# SparkFun_NEO-M8T.net
KiCad netlist of a schematic drawn in EAGLE
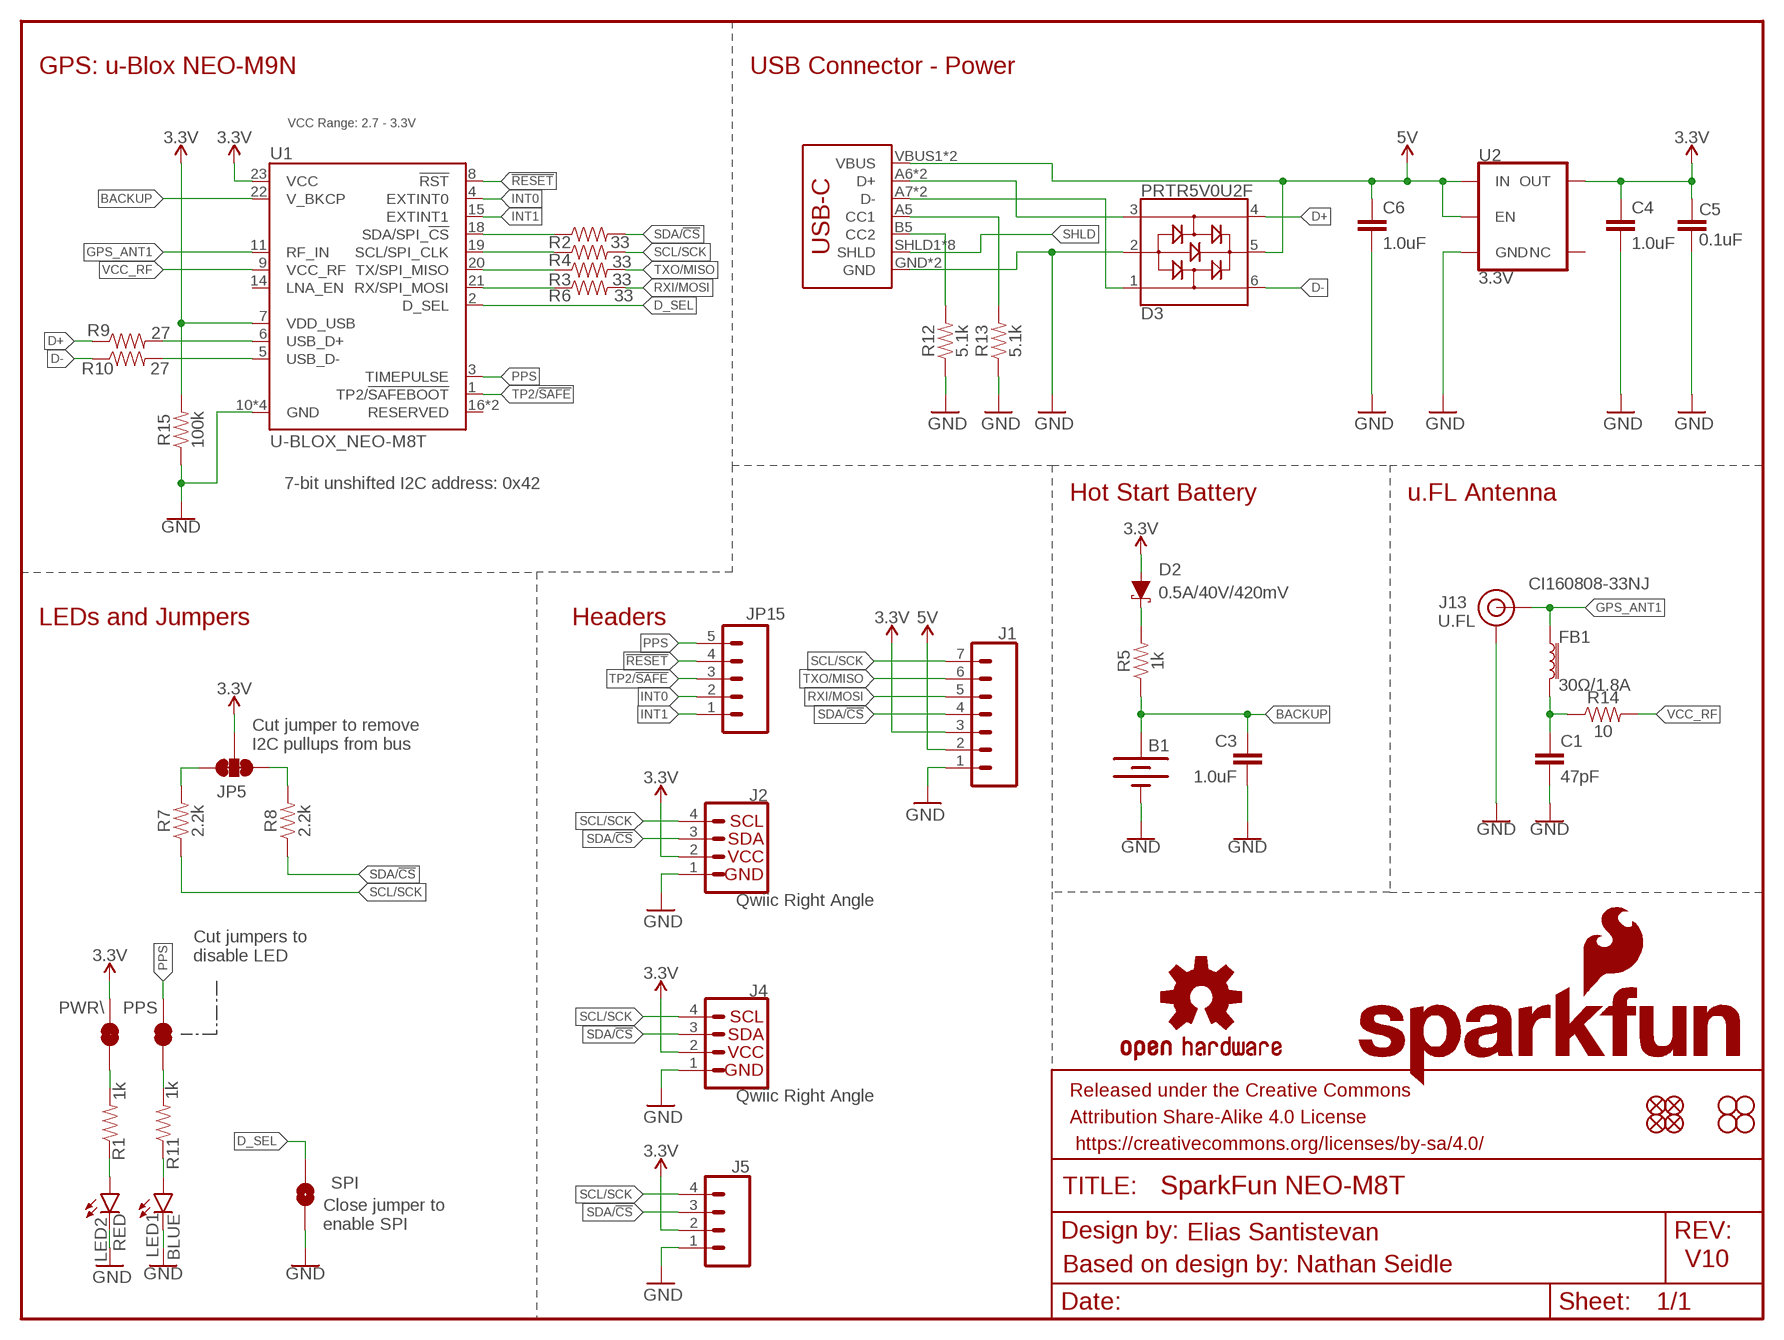
[diagram p0: schematic, sheet 1]

(export (version "E")
  (design (tool "Eeschema 10.0.6"))
  (components
    (comp (ref "B1")
      (value "6.8MM_COIN_CELL")
      (footprint "eagle-import:ML414H_IV01E")
      (libsource (lib "eagle-import") (part "ML414H_IV01E_BATTERY"))
    )
    (comp (ref "C1")
      (value "47pF")
      (footprint "eagle-import:0603")
      (libsource (lib "eagle-import") (part "47PF-0603-50V-5%"))
    )
    (comp (ref "C3")
      (value "1.0uF")
      (footprint "eagle-import:0603")
      (libsource (lib "eagle-import") (part "1.0UF-0603-16V-10%"))
    )
    (comp (ref "C4")
      (value "1.0uF")
      (footprint "eagle-import:0603")
      (libsource (lib "eagle-import") (part "1.0UF-0603-16V-10%"))
    )
    (comp (ref "C5")
      (value "0.1uF")
      (footprint "eagle-import:0603")
      (libsource (lib "eagle-import") (part "0.1UF-0603-25V-(+80/-20%)"))
    )
    (comp (ref "C6")
      (value "1.0uF")
      (footprint "eagle-import:0603")
      (libsource (lib "eagle-import") (part "1.0UF-0603-16V-10%"))
    )
    (comp (ref "D2")
      (value "0.5A/40V/420mV")
      (footprint "eagle-import:SOD-323")
      (libsource (lib "eagle-import") (part "DIODE-SCHOTTKY-PMEG4005EJ"))
    )
    (comp (ref "D3")
      (value "PRTR5V0U2F")
      (footprint "eagle-import:SOT886")
      (libsource (lib "eagle-import") (part "PRTR5V0U2F"))
    )
    (comp (ref "FB1")
      (value "30Ω/1.8A")
      (footprint "eagle-import:0603")
      (libsource (lib "eagle-import") (part "FERRITE_BEAD-0603"))
    )
    (comp (ref "FRAME1")
      (value "FRAME-LETTER")
      (footprint "eagle-import:CREATIVE_COMMONS")
      (libsource (lib "eagle-import") (part "FRAME-LETTER"))
    )
    (comp (ref "J1")
      (value "CONN_07NO_SILK")
      (footprint "eagle-import:1X07_NO_SILK")
      (libsource (lib "eagle-import") (part "CONN_07NO_SILK"))
    )
    (comp (ref "J2")
      (value "Qwiic Right Angle")
      (footprint "eagle-import:JST04_1MM_RA")
      (libsource (lib "eagle-import") (part "I2C_STANDARDQWIIC"))
    )
    (comp (ref "J3")
      (value "USB_C2-LAYER")
      (footprint "eagle-import:USB-C-16P")
      (libsource (lib "eagle-import") (part "USB_C2-LAYER"))
    )
    (comp (ref "J4")
      (value "Qwiic Right Angle")
      (footprint "eagle-import:JST04_1MM_RA")
      (libsource (lib "eagle-import") (part "I2C_STANDARDQWIIC"))
    )
    (comp (ref "J5")
      (value "CONN_041X04_NO_SILK")
      (footprint "eagle-import:1X04_NO_SILK")
      (libsource (lib "eagle-import") (part "CONN_041X04_NO_SILK"))
    )
    (comp (ref "J13")
      (value "U.FL")
      (footprint "eagle-import:U.FL")
      (libsource (lib "eagle-import") (part "U.FL2PIN"))
    )
    (comp (ref "JP5")
      (value "JUMPER-SMT_3_2-NC_TRACE_SILK")
      (footprint "eagle-import:SMT-JUMPER_3_2-NC_TRACE_SILK")
      (libsource (lib "eagle-import") (part "JUMPER-SMT_3_2-NC_TRACE_SILK"))
    )
    (comp (ref "JP15")
      (value "CONN_05NO_SILK")
      (footprint "eagle-import:1X05_NO_SILK")
      (libsource (lib "eagle-import") (part "CONN_05NO_SILK"))
    )
    (comp (ref "JP21")
      (value "FIDUCIALUFIDUCIAL")
      (footprint "eagle-import:MICRO-FIDUCIAL")
      (libsource (lib "eagle-import") (part "FIDUCIALUFIDUCIAL"))
    )
    (comp (ref "JP31")
      (value "STAND-OFF")
      (footprint "eagle-import:STAND-OFF")
      (libsource (lib "eagle-import") (part "STAND-OFF"))
    )
    (comp (ref "JP41")
      (value "STAND-OFF")
      (footprint "eagle-import:STAND-OFF")
      (libsource (lib "eagle-import") (part "STAND-OFF"))
    )
    (comp (ref "JP61")
      (value "FIDUCIALUFIDUCIAL")
      (footprint "eagle-import:MICRO-FIDUCIAL")
      (libsource (lib "eagle-import") (part "FIDUCIALUFIDUCIAL"))
    )
    (comp (ref "JP71")
      (value "FIDUCIALUFIDUCIAL")
      (footprint "eagle-import:MICRO-FIDUCIAL")
      (libsource (lib "eagle-import") (part "FIDUCIALUFIDUCIAL"))
    )
    (comp (ref "JP81")
      (value "FIDUCIALUFIDUCIAL")
      (footprint "eagle-import:MICRO-FIDUCIAL")
      (libsource (lib "eagle-import") (part "FIDUCIALUFIDUCIAL"))
    )
    (comp (ref "JP91")
      (value "STAND-OFF")
      (footprint "eagle-import:STAND-OFF")
      (libsource (lib "eagle-import") (part "STAND-OFF"))
    )
    (comp (ref "JP101")
      (value "STAND-OFF")
      (footprint "eagle-import:STAND-OFF")
      (libsource (lib "eagle-import") (part "STAND-OFF"))
    )
    (comp (ref "LED1")
      (value "BLUE")
      (footprint "eagle-import:LED-0603")
      (libsource (lib "eagle-import") (part "LED-BLUE0603"))
    )
    (comp (ref "LED2")
      (value "RED")
      (footprint "eagle-import:LED-0603")
      (libsource (lib "eagle-import") (part "LED-RED0603"))
    )
    (comp (ref "LOGO1")
      (value "OSHW-LOGOMINI")
      (footprint "eagle-import:OSHW-LOGO-MINI")
      (libsource (lib "eagle-import") (part "OSHW-LOGOMINI"))
    )
    (comp (ref "LOGO2")
      (value "SFE_LOGO_NAME_FLAME.1_INCH")
      (footprint "eagle-import:SFE_LOGO_NAME_FLAME_.1")
      (libsource (lib "eagle-import") (part "SFE_LOGO_NAME_FLAME.1_INCH"))
    )
    (comp (ref "PPS")
      (value "JUMPER-SMT_2_NC_TRACE_SILK")
      (footprint "eagle-import:SMT-JUMPER_2_NC_TRACE_SILK")
      (libsource (lib "eagle-import") (part "JUMPER-SMT_2_NC_TRACE_SILK"))
    )
    (comp (ref "PWR\\")
      (value "JUMPER-SMT_2_NC_TRACE_SILK")
      (footprint "eagle-import:SMT-JUMPER_2_NC_TRACE_SILK")
      (libsource (lib "eagle-import") (part "JUMPER-SMT_2_NC_TRACE_SILK"))
    )
    (comp (ref "R1")
      (value "1k")
      (footprint "eagle-import:0603")
      (libsource (lib "eagle-import") (part "1KOHM-0603-1/10W-1%"))
    )
    (comp (ref "R2")
      (value "33")
      (footprint "eagle-import:0603")
      (libsource (lib "eagle-import") (part "33OHM-0603-1/10W-1%"))
    )
    (comp (ref "R3")
      (value "33")
      (footprint "eagle-import:0603")
      (libsource (lib "eagle-import") (part "33OHM-0603-1/10W-1%"))
    )
    (comp (ref "R4")
      (value "33")
      (footprint "eagle-import:0603")
      (libsource (lib "eagle-import") (part "33OHM-0603-1/10W-1%"))
    )
    (comp (ref "R5")
      (value "1k")
      (footprint "eagle-import:0603")
      (libsource (lib "eagle-import") (part "1KOHM-0603-1/10W-1%"))
    )
    (comp (ref "R6")
      (value "33")
      (footprint "eagle-import:0603")
      (libsource (lib "eagle-import") (part "33OHM-0603-1/10W-1%"))
    )
    (comp (ref "R7")
      (value "2.2k")
      (footprint "eagle-import:0603")
      (libsource (lib "eagle-import") (part "2.2KOHM-0603-1/10W-1%"))
    )
    (comp (ref "R8")
      (value "2.2k")
      (footprint "eagle-import:0603")
      (libsource (lib "eagle-import") (part "2.2KOHM-0603-1/10W-1%"))
    )
    (comp (ref "R9")
      (value "27")
      (footprint "eagle-import:0603")
      (libsource (lib "eagle-import") (part "27OHM-0603-1/10W-1%"))
    )
    (comp (ref "R10")
      (value "27")
      (footprint "eagle-import:0603")
      (libsource (lib "eagle-import") (part "27OHM-0603-1/10W-1%"))
    )
    (comp (ref "R11")
      (value "1k")
      (footprint "eagle-import:0603")
      (libsource (lib "eagle-import") (part "1KOHM-0603-1/10W-1%"))
    )
    (comp (ref "R12")
      (value "5.1k")
      (footprint "eagle-import:0603")
      (libsource (lib "eagle-import") (part "5.1KOHM5.1KOHM-0603-1/10W-1%"))
    )
    (comp (ref "R13")
      (value "5.1k")
      (footprint "eagle-import:0603")
      (libsource (lib "eagle-import") (part "5.1KOHM5.1KOHM-0603-1/10W-1%"))
    )
    (comp (ref "R14")
      (value "10")
      (footprint "eagle-import:0603")
      (libsource (lib "eagle-import") (part "10OHM-0603-1/10W-1%"))
    )
    (comp (ref "R15")
      (value "100k")
      (footprint "eagle-import:0603")
      (libsource (lib "eagle-import") (part "100KOHM-0603-1/10W-1%"))
    )
    (comp (ref "SPI")
      (value "JUMPER-SMT_2_NO_SILK")
      (footprint "eagle-import:SMT-JUMPER_2_NO_SILK")
      (libsource (lib "eagle-import") (part "JUMPER-SMT_2_NO_SILK"))
    )
    (comp (ref "U1")
      (value "U-BLOX_NEO-M8T")
      (footprint "eagle-import:NEO-M9N_M8T")
      (libsource (lib "eagle-import") (part "U-BLOX_NEO-M8T"))
    )
    (comp (ref "U2")
      (value "3.3V")
      (footprint "eagle-import:SOT23-5")
      (libsource (lib "eagle-import") (part "V_REG_AP2112K-3.3V"))
    )
  )
  (nets
    (net (code "1") (name "/SDA{slash}~{CS}") (class "Default")
      (node (ref "J1") (pin "4") (pinfunction "4_4") (pintype "passive"))
      (node (ref "J2") (pin "3") (pinfunction "3_3") (pintype "passive"))
      (node (ref "J4") (pin "3") (pinfunction "3_3") (pintype "passive"))
      (node (ref "J5") (pin "3") (pinfunction "3_3") (pintype "passive"))
      (node (ref "R2") (pin "2") (pinfunction "2_2") (pintype "passive"))
      (node (ref "R8") (pin "1") (pinfunction "1_1") (pintype "passive"))
    )
    (net (code "2") (name "/TP2{slash}~{SAFE}") (class "Default")
      (node (ref "JP15") (pin "3") (pinfunction "3_3") (pintype "passive"))
      (node (ref "U1") (pin "1") (pinfunction "TP2/~{SAFEBOOT}_1") (pintype "bidirectional"))
    )
    (net (code "3") (name "/~{RESET}") (class "Default")
      (node (ref "JP15") (pin "4") (pinfunction "4_4") (pintype "passive"))
      (node (ref "U1") (pin "8") (pinfunction "~{RST}_8") (pintype "bidirectional"))
    )
    (net (code "4") (name "3.3V") (class "Default")
      (node (ref "C4") (pin "1") (pinfunction "1_1") (pintype "passive"))
      (node (ref "C5") (pin "2") (pinfunction "2_2") (pintype "passive"))
      (node (ref "D2") (pin "A") (pinfunction "A_A") (pintype "passive"))
      (node (ref "J1") (pin "3") (pinfunction "3_3") (pintype "passive"))
      (node (ref "J2") (pin "2") (pinfunction "2_2") (pintype "power_in"))
      (node (ref "J4") (pin "2") (pinfunction "2_2") (pintype "power_in"))
      (node (ref "J5") (pin "2") (pinfunction "2_2") (pintype "passive"))
      (node (ref "JP5") (pin "2") (pinfunction "2_2") (pintype "passive"))
      (node (ref "PWR\\") (pin "2") (pinfunction "2_2") (pintype "passive"))
      (node (ref "R15") (pin "2") (pinfunction "2_2") (pintype "passive"))
      (node (ref "U1") (pin "23") (pinfunction "VCC_23") (pintype "bidirectional"))
      (node (ref "U1") (pin "7") (pinfunction "VDD_USB_7") (pintype "bidirectional"))
      (node (ref "U2") (pin "5") (pinfunction "OUT_5") (pintype "passive"))
    )
    (net (code "5") (name "5V") (class "Default")
      (node (ref "C6") (pin "1") (pinfunction "1_1") (pintype "passive"))
      (node (ref "D3") (pin "5") (pinfunction "5_5") (pintype "bidirectional"))
      (node (ref "J1") (pin "2") (pinfunction "2_2") (pintype "passive"))
      (node (ref "J3") (pin "VBUS1") (pinfunction "VBUS_VBUS1") (pintype "bidirectional"))
      (node (ref "J3") (pin "VBUS2") (pinfunction "VBUS_VBUS2") (pintype "bidirectional"))
      (node (ref "U2") (pin "1") (pinfunction "IN_1") (pintype "input"))
      (node (ref "U2") (pin "3") (pinfunction "EN_3") (pintype "input"))
    )
    (net (code "6") (name "BACKUP") (class "Default")
      (node (ref "B1") (pin "+") (pinfunction "+_+") (pintype "power_in"))
      (node (ref "C3") (pin "1") (pinfunction "1_1") (pintype "passive"))
      (node (ref "R5") (pin "1") (pinfunction "1_1") (pintype "passive"))
      (node (ref "U1") (pin "22") (pinfunction "V_BKCP_22") (pintype "bidirectional"))
    )
    (net (code "7") (name "D+") (class "Default")
      (node (ref "D3") (pin "4") (pinfunction "4_4") (pintype "bidirectional"))
      (node (ref "R9") (pin "1") (pinfunction "1_1") (pintype "passive"))
    )
    (net (code "8") (name "D-") (class "Default")
      (node (ref "D3") (pin "6") (pinfunction "6_6") (pintype "bidirectional"))
      (node (ref "R10") (pin "1") (pinfunction "1_1") (pintype "passive"))
    )
    (net (code "9") (name "D_SEL") (class "Default")
      (node (ref "SPI") (pin "2") (pinfunction "2_2") (pintype "passive"))
      (node (ref "U1") (pin "2") (pinfunction "D_SEL_2") (pintype "bidirectional"))
    )
    (net (code "10") (name "GND") (class "Default")
      (node (ref "B1") (pin "-") (pinfunction "-_-") (pintype "power_in"))
      (node (ref "C1") (pin "2") (pinfunction "2_2") (pintype "passive"))
      (node (ref "C3") (pin "2") (pinfunction "2_2") (pintype "passive"))
      (node (ref "C4") (pin "2") (pinfunction "2_2") (pintype "passive"))
      (node (ref "C5") (pin "1") (pinfunction "1_1") (pintype "passive"))
      (node (ref "C6") (pin "2") (pinfunction "2_2") (pintype "passive"))
      (node (ref "D3") (pin "2") (pinfunction "2_2") (pintype "bidirectional"))
      (node (ref "J1") (pin "1") (pinfunction "1_1") (pintype "passive"))
      (node (ref "J13") (pin "1") (pinfunction "GND_1") (pintype "bidirectional"))
      (node (ref "J13") (pin "2") (pinfunction "GND_2") (pintype "bidirectional"))
      (node (ref "J2") (pin "1") (pinfunction "1_1") (pintype "power_in"))
      (node (ref "J3") (pin "GND") (pinfunction "GND_GND") (pintype "bidirectional"))
      (node (ref "J3") (pin "GND2") (pinfunction "GND_GND2") (pintype "bidirectional"))
      (node (ref "J4") (pin "1") (pinfunction "1_1") (pintype "power_in"))
      (node (ref "J5") (pin "1") (pinfunction "1_1") (pintype "passive"))
      (node (ref "LED1") (pin "C") (pinfunction "C_C") (pintype "passive"))
      (node (ref "LED2") (pin "C") (pinfunction "C_C") (pintype "passive"))
      (node (ref "R12") (pin "1") (pinfunction "1_1") (pintype "passive"))
      (node (ref "R13") (pin "1") (pinfunction "1_1") (pintype "passive"))
      (node (ref "R15") (pin "1") (pinfunction "1_1") (pintype "passive"))
      (node (ref "SPI") (pin "1") (pinfunction "1_1") (pintype "passive"))
      (node (ref "U1") (pin "10") (pinfunction "GND_10") (pintype "bidirectional"))
      (node (ref "U1") (pin "12") (pinfunction "GND_12") (pintype "bidirectional"))
      (node (ref "U1") (pin "13") (pinfunction "GND_13") (pintype "bidirectional"))
      (node (ref "U1") (pin "24") (pinfunction "GND_24") (pintype "bidirectional"))
      (node (ref "U2") (pin "2") (pinfunction "GND_2") (pintype "input"))
    )
    (net (code "11") (name "GPS_ANT1") (class "Default")
      (node (ref "FB1") (pin "1") (pinfunction "1_1") (pintype "passive"))
      (node (ref "J13") (pin "FEED") (pinfunction "SIGNAL_FEED") (pintype "bidirectional"))
      (node (ref "U1") (pin "11") (pinfunction "RF_IN_11") (pintype "bidirectional"))
    )
    (net (code "12") (name "INT0") (class "Default")
      (node (ref "JP15") (pin "2") (pinfunction "2_2") (pintype "passive"))
      (node (ref "U1") (pin "4") (pinfunction "EXTINT0_4") (pintype "bidirectional"))
    )
    (net (code "13") (name "INT1") (class "Default")
      (node (ref "JP15") (pin "1") (pinfunction "1_1") (pintype "passive"))
      (node (ref "U1") (pin "15") (pinfunction "EXTINT1_15") (pintype "bidirectional"))
    )
    (net (code "14") (name "Net-(C1-Pad1)") (class "Default")
      (node (ref "C1") (pin "1") (pinfunction "1_1") (pintype "passive"))
      (node (ref "FB1") (pin "2") (pinfunction "2_2") (pintype "passive"))
      (node (ref "R14") (pin "1") (pinfunction "1_1") (pintype "passive"))
    )
    (net (code "15") (name "Net-(D2-PadC)") (class "Default")
      (node (ref "D2") (pin "C") (pinfunction "C_C") (pintype "passive"))
      (node (ref "R5") (pin "2") (pinfunction "2_2") (pintype "passive"))
    )
    (net (code "16") (name "Net-(D3-Pad1)") (class "Default")
      (node (ref "D3") (pin "1") (pinfunction "1_1") (pintype "bidirectional"))
      (node (ref "J3") (pin "A7") (pinfunction "D-_A7") (pintype "bidirectional"))
      (node (ref "J3") (pin "B7") (pinfunction "D-_B7") (pintype "bidirectional"))
    )
    (net (code "17") (name "Net-(D3-Pad3)") (class "Default")
      (node (ref "D3") (pin "3") (pinfunction "3_3") (pintype "bidirectional"))
      (node (ref "J3") (pin "A6") (pinfunction "D+_A6") (pintype "bidirectional"))
      (node (ref "J3") (pin "B6") (pinfunction "D+_B6") (pintype "bidirectional"))
    )
    (net (code "18") (name "Net-(J3-CC1)") (class "Default")
      (node (ref "J3") (pin "A5") (pinfunction "CC1_A5") (pintype "bidirectional"))
      (node (ref "R13") (pin "2") (pinfunction "2_2") (pintype "passive"))
    )
    (net (code "19") (name "Net-(J3-CC2)") (class "Default")
      (node (ref "J3") (pin "B5") (pinfunction "CC2_B5") (pintype "bidirectional"))
      (node (ref "R12") (pin "2") (pinfunction "2_2") (pintype "passive"))
    )
    (net (code "20") (name "Net-(JP5-Pad1)") (class "Default")
      (node (ref "JP5") (pin "1") (pinfunction "1_1") (pintype "passive"))
      (node (ref "R8") (pin "2") (pinfunction "2_2") (pintype "passive"))
    )
    (net (code "21") (name "Net-(JP5-Pad3)") (class "Default")
      (node (ref "JP5") (pin "3") (pinfunction "3_3") (pintype "passive"))
      (node (ref "R7") (pin "2") (pinfunction "2_2") (pintype "passive"))
    )
    (net (code "22") (name "Net-(LED1-PadA)") (class "Default")
      (node (ref "LED1") (pin "A") (pinfunction "A_A") (pintype "passive"))
      (node (ref "R11") (pin "1") (pinfunction "1_1") (pintype "passive"))
    )
    (net (code "23") (name "Net-(LED2-PadA)") (class "Default")
      (node (ref "LED2") (pin "A") (pinfunction "A_A") (pintype "passive"))
      (node (ref "R1") (pin "1") (pinfunction "1_1") (pintype "passive"))
    )
    (net (code "24") (name "Net-(PPS-Pad1)") (class "Default")
      (node (ref "PPS") (pin "1") (pinfunction "1_1") (pintype "passive"))
      (node (ref "R11") (pin "2") (pinfunction "2_2") (pintype "passive"))
    )
    (net (code "25") (name "Net-(PWR\\-Pad1)") (class "Default")
      (node (ref "PWR\\") (pin "1") (pinfunction "1_1") (pintype "passive"))
      (node (ref "R1") (pin "2") (pinfunction "2_2") (pintype "passive"))
    )
    (net (code "26") (name "Net-(U1-RX{slash}SPI_MOSI)") (class "Default")
      (node (ref "R6") (pin "1") (pinfunction "1_1") (pintype "passive"))
      (node (ref "U1") (pin "21") (pinfunction "RX/SPI_MOSI_21") (pintype "bidirectional"))
    )
    (net (code "27") (name "Net-(U1-SCL{slash}SPI_CLK)") (class "Default")
      (node (ref "R4") (pin "1") (pinfunction "1_1") (pintype "passive"))
      (node (ref "U1") (pin "19") (pinfunction "SCL/SPI_CLK_19") (pintype "bidirectional"))
    )
    (net (code "28") (name "Net-(U1-SDA{slash}SPI_~{CS})") (class "Default")
      (node (ref "R2") (pin "1") (pinfunction "1_1") (pintype "passive"))
      (node (ref "U1") (pin "18") (pinfunction "SDA/SPI_~{CS}_18") (pintype "bidirectional"))
    )
    (net (code "29") (name "Net-(U1-TX{slash}SPI_MISO)") (class "Default")
      (node (ref "R3") (pin "1") (pinfunction "1_1") (pintype "passive"))
      (node (ref "U1") (pin "20") (pinfunction "TX/SPI_MISO_20") (pintype "bidirectional"))
    )
    (net (code "30") (name "Net-(U1-USB_D+)") (class "Default")
      (node (ref "R9") (pin "2") (pinfunction "2_2") (pintype "passive"))
      (node (ref "U1") (pin "6") (pinfunction "USB_D+_6") (pintype "bidirectional"))
    )
    (net (code "31") (name "Net-(U1-USB_D-)") (class "Default")
      (node (ref "R10") (pin "2") (pinfunction "2_2") (pintype "passive"))
      (node (ref "U1") (pin "5") (pinfunction "USB_D-_5") (pintype "bidirectional"))
    )
    (net (code "32") (name "PPS") (class "Default")
      (node (ref "JP15") (pin "5") (pinfunction "5_5") (pintype "passive"))
      (node (ref "PPS") (pin "2") (pinfunction "2_2") (pintype "passive"))
      (node (ref "U1") (pin "3") (pinfunction "TIMEPULSE_3") (pintype "bidirectional"))
    )
    (net (code "33") (name "RXI{slash}MOSI") (class "Default")
      (node (ref "J1") (pin "5") (pinfunction "5_5") (pintype "passive"))
      (node (ref "R6") (pin "2") (pinfunction "2_2") (pintype "passive"))
    )
    (net (code "34") (name "SCL{slash}SCK") (class "Default")
      (node (ref "J1") (pin "7") (pinfunction "7_7") (pintype "passive"))
      (node (ref "J2") (pin "4") (pinfunction "4_4") (pintype "passive"))
      (node (ref "J4") (pin "4") (pinfunction "4_4") (pintype "passive"))
      (node (ref "J5") (pin "4") (pinfunction "4_4") (pintype "passive"))
      (node (ref "R4") (pin "2") (pinfunction "2_2") (pintype "passive"))
      (node (ref "R7") (pin "1") (pinfunction "1_1") (pintype "passive"))
    )
    (net (code "35") (name "SHLD") (class "Default")
      (node (ref "J3") (pin "SHLD1") (pinfunction "SHLD_SHLD1") (pintype "bidirectional"))
      (node (ref "J3") (pin "SHLD2") (pinfunction "SHLD_SHLD2") (pintype "bidirectional"))
      (node (ref "J3") (pin "SHLD3") (pinfunction "SHLD_SHLD3") (pintype "bidirectional"))
      (node (ref "J3") (pin "SHLD4") (pinfunction "SHLD_SHLD4") (pintype "bidirectional"))
      (node (ref "J3") (pin "SHLD5") (pinfunction "SHLD_SHLD5") (pintype "bidirectional"))
      (node (ref "J3") (pin "SHLD6") (pinfunction "SHLD_SHLD6") (pintype "bidirectional"))
      (node (ref "J3") (pin "SHLD7") (pinfunction "SHLD_SHLD7") (pintype "bidirectional"))
      (node (ref "J3") (pin "SHLD8") (pinfunction "SHLD_SHLD8") (pintype "bidirectional"))
    )
    (net (code "36") (name "TXO{slash}MISO") (class "Default")
      (node (ref "J1") (pin "6") (pinfunction "6_6") (pintype "passive"))
      (node (ref "R3") (pin "2") (pinfunction "2_2") (pintype "passive"))
    )
    (net (code "37") (name "VCC_RF") (class "Default")
      (node (ref "R14") (pin "2") (pinfunction "2_2") (pintype "passive"))
      (node (ref "U1") (pin "9") (pinfunction "VCC_RF_9") (pintype "bidirectional"))
    )
    (net (code "38") (name "unconnected-(U1-LNA_EN-Pad14)") (class "Default")
      (node (ref "U1") (pin "14") (pinfunction "LNA_EN_14") (pintype "bidirectional"))
    )
    (net (code "39") (name "unconnected-(U1-RESERVED-Pad16)") (class "Default")
      (node (ref "U1") (pin "16") (pinfunction "RESERVED_16") (pintype "no_connect"))
    )
    (net (code "40") (name "unconnected-(U1-RESERVED-Pad17)") (class "Default")
      (node (ref "U1") (pin "17") (pinfunction "RESERVED_17") (pintype "no_connect"))
    )
    (net (code "41") (name "unconnected-(U2-NC-Pad4)") (class "Default")
      (node (ref "U2") (pin "4") (pinfunction "NC_4") (pintype "no_connect"))
    )
  )
)
